# ST_LINK_V3E.net
KiCad netlist of a schematic drawn in Altium Designer
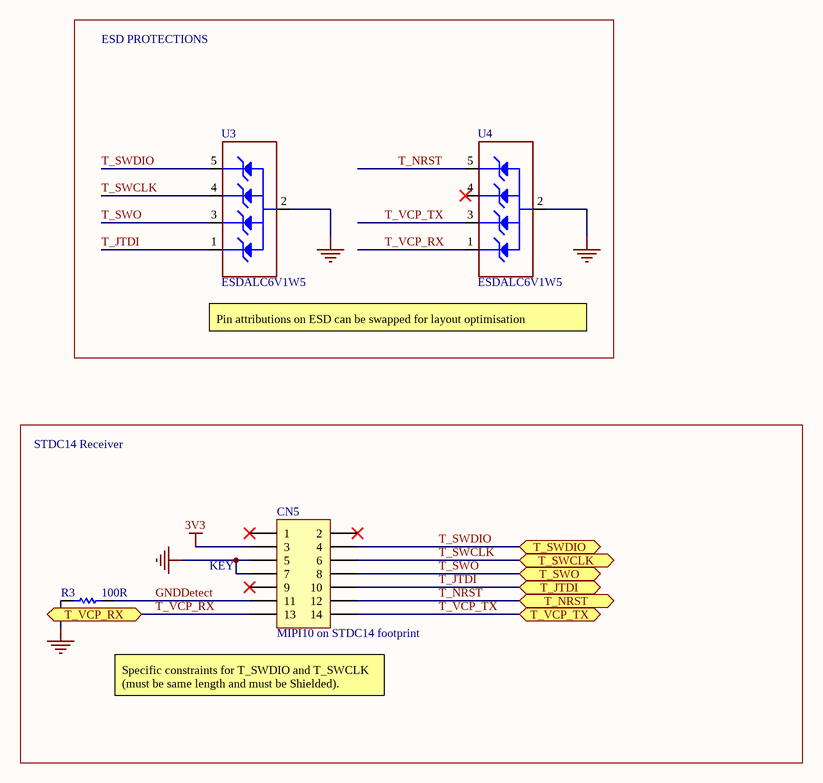
[diagram p0: ST_LINK_V3E.SchDoc]

(export (version "E")
  (design (tool "Eeschema 10.0.6"))
  (components
    (comp (ref "CN5")
      (value "MIPI10 on STDC14 footprint")
      (footprint "CON_STDC14_Receiver_MEDIUM_WITH_MIPI10_3D")
      (fields
        (field (name "INTERNAL_PART_NUMBER") "MCD-01226")
        (field (name "MANUFACTURER_PART_NUMBER") "FTSH-105-01-L-DV-K")
        (field (name "MANUFACTURER") "SAMTEC")
        (field (name "PROVIDED_BY") "SUBCO")
      )
      (libsource (lib "MCD_PARTS_database") (part "Header 7x2"))
    )
    (comp (ref "R3")
      (value "100R")
      (footprint "R0402")
      (description "Resistor,100R,0402,1%,1/16W")
      (fields
        (field (name "INTERNAL_PART_NUMBER") "MCD-00119")
        (field (name "MANUFACTURER_PART_NUMBER") "RC0402FR-07100RL")
        (field (name "PROVIDED_BY") "SUBCO")
      )
      (libsource (lib "MCD_PARTS_database") (part "Resistor"))
    )
    (comp (ref "U3")
      (value "ESDALC6V1W5")
      (footprint "ESD_SOT323-5L")
      (description "Dual Transil array for ESD protection")
      (fields
        (field (name "INTERNAL_PART_NUMBER") "MCD-00136")
        (field (name "MANUFACTURER") "STMICROELECTRONICS")
        (field (name "PROVIDED_BY") "SUBCO with ST control")
      )
      (libsource (lib "MCD_PARTS_database") (part "ESDALC6V1W5"))
    )
    (comp (ref "U4")
      (value "ESDALC6V1W5")
      (footprint "ESD_SOT323-5L")
      (description "Dual Transil array for ESD protection")
      (fields
        (field (name "INTERNAL_PART_NUMBER") "MCD-00136")
        (field (name "MANUFACTURER") "STMICROELECTRONICS")
        (field (name "PROVIDED_BY") "SUBCO with ST control")
      )
      (libsource (lib "MCD_PARTS_database") (part "ESDALC6V1W5"))
    )
  )
  (nets
    (net (code "1") (name "/GNDDetect") (class "Default")
      (node (ref "CN5") (pin "11") (pinfunction "11_11") (pintype "passive"))
      (node (ref "R3") (pin "2") (pinfunction "2_2") (pintype "passive"))
    )
    (net (code "2") (name "/T_JTDI") (class "Default")
      (node (ref "CN5") (pin "10") (pinfunction "10_10") (pintype "passive"))
      (node (ref "U3") (pin "1") (pinfunction "IO1_1") (pintype "passive"))
    )
    (net (code "3") (name "/T_NRST") (class "Default")
      (node (ref "CN5") (pin "12") (pinfunction "12_12") (pintype "passive"))
      (node (ref "U4") (pin "5") (pinfunction "IO4_5") (pintype "passive"))
    )
    (net (code "4") (name "/T_SWCLK") (class "Default")
      (node (ref "CN5") (pin "6") (pinfunction "6_6") (pintype "passive"))
      (node (ref "U3") (pin "4") (pinfunction "IO3_4") (pintype "passive"))
    )
    (net (code "5") (name "/T_SWDIO") (class "Default")
      (node (ref "CN5") (pin "4") (pinfunction "4_4") (pintype "passive"))
      (node (ref "U3") (pin "5") (pinfunction "IO4_5") (pintype "passive"))
    )
    (net (code "6") (name "/T_SWO") (class "Default")
      (node (ref "CN5") (pin "8") (pinfunction "8_8") (pintype "passive"))
      (node (ref "U3") (pin "3") (pinfunction "IO2_3") (pintype "passive"))
    )
    (net (code "7") (name "/T_VCP_RX") (class "Default")
      (node (ref "CN5") (pin "13") (pinfunction "13_13") (pintype "passive"))
      (node (ref "U4") (pin "1") (pinfunction "IO1_1") (pintype "passive"))
    )
    (net (code "8") (name "/T_VCP_TX") (class "Default")
      (node (ref "CN5") (pin "14") (pinfunction "14_14") (pintype "passive"))
      (node (ref "U4") (pin "3") (pinfunction "IO2_3") (pintype "passive"))
    )
    (net (code "9") (name "3V3") (class "Default")
      (node (ref "CN5") (pin "3") (pinfunction "3_3") (pintype "passive"))
    )
    (net (code "10") (name "GND") (class "Default")
      (node (ref "CN5") (pin "5") (pinfunction "5_5") (pintype "passive"))
      (node (ref "CN5") (pin "7") (pinfunction "7_7") (pintype "passive"))
      (node (ref "R3") (pin "1") (pinfunction "1_1") (pintype "passive"))
      (node (ref "U3") (pin "2") (pinfunction "GND_2") (pintype "passive"))
      (node (ref "U4") (pin "2") (pinfunction "GND_2") (pintype "passive"))
    )
    (net (code "11") (name "unconnected-(CN5-Pad1)") (class "Default")
      (node (ref "CN5") (pin "1") (pinfunction "1_1") (pintype "passive+no_connect"))
    )
    (net (code "12") (name "unconnected-(CN5-Pad2)") (class "Default")
      (node (ref "CN5") (pin "2") (pinfunction "2_2") (pintype "passive+no_connect"))
    )
    (net (code "13") (name "unconnected-(CN5-Pad9)") (class "Default")
      (node (ref "CN5") (pin "9") (pinfunction "9_9") (pintype "passive+no_connect"))
    )
    (net (code "14") (name "unconnected-(U4-IO3-Pad4)") (class "Default")
      (node (ref "U4") (pin "4") (pinfunction "IO3_4") (pintype "passive+no_connect"))
    )
  )
)
